# Power_And_Voltage_Shifters.net
KiCad netlist of a schematic drawn in Altium Designer
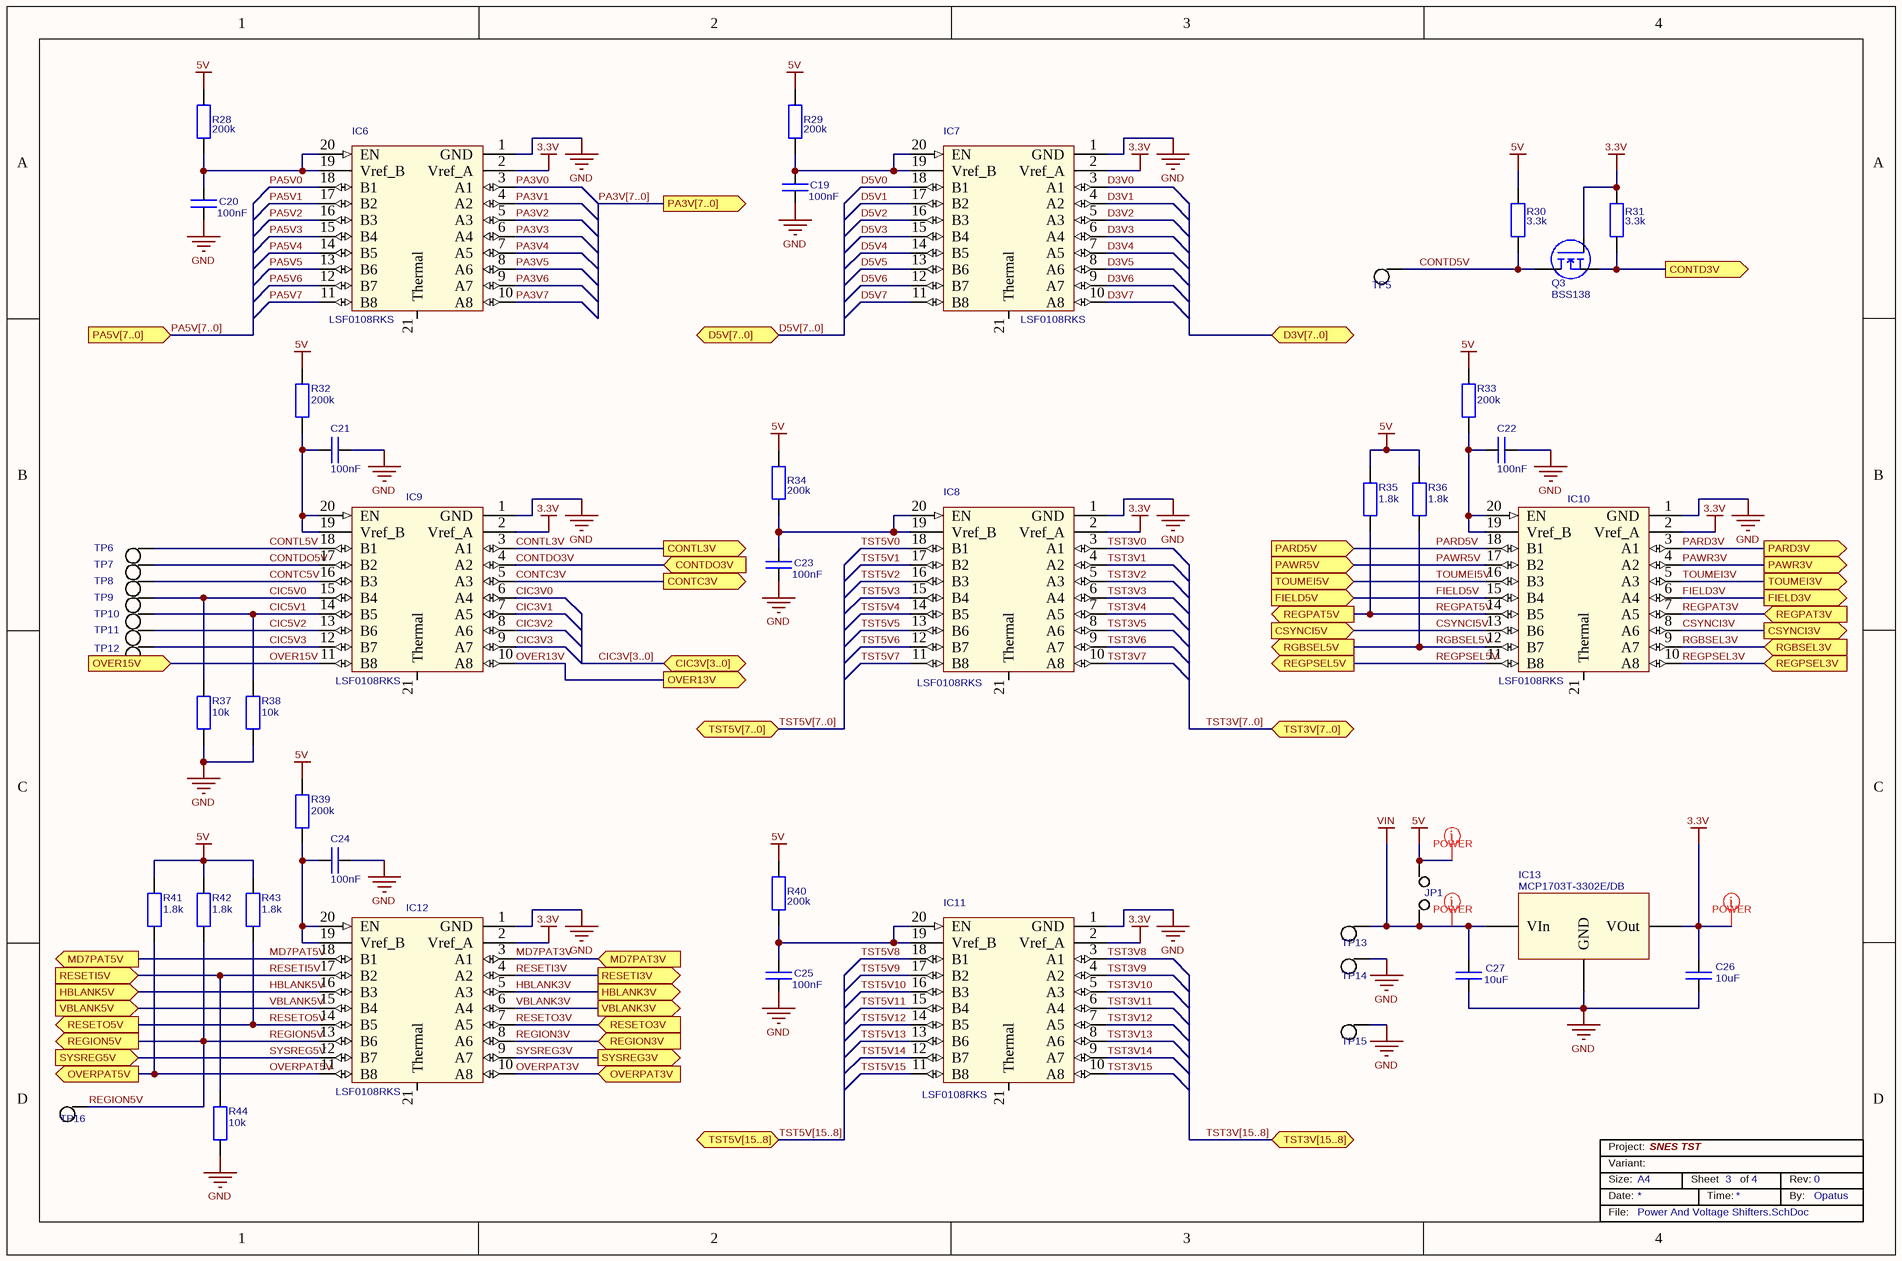
[diagram p0: Power And Voltage Shifters.SchDoc]

(export (version "E")
  (design (tool "Eeschema 10.0.6"))
  (components
    (comp (ref "C19")
      (value "100nF")
      (footprint "Cap_0402_Chip")
      (fields
        (field (name "TOLERANCE") "±20%")
        (field (name "Comment") "Ceramic Capacitor 100nF 10V ±20% X7R 0402")
      )
      (libsource (lib "PCB") (part "Capacitor"))
    )
    (comp (ref "C20")
      (value "100nF")
      (footprint "Cap_0402_Chip")
      (fields
        (field (name "TOLERANCE") "±20%")
        (field (name "Comment") "Ceramic Capacitor 100nF 10V ±20% X7R 0402")
      )
      (libsource (lib "PCB") (part "Capacitor"))
    )
    (comp (ref "C21")
      (value "100nF")
      (footprint "Cap_0402_Chip")
      (fields
        (field (name "TOLERANCE") "±20%")
        (field (name "Comment") "Ceramic Capacitor 100nF 10V ±20% X7R 0402")
      )
      (libsource (lib "PCB") (part "Capacitor"))
    )
    (comp (ref "C22")
      (value "100nF")
      (footprint "Cap_0402_Chip")
      (fields
        (field (name "TOLERANCE") "±20%")
        (field (name "Comment") "Ceramic Capacitor 100nF 10V ±20% X7R 0402")
      )
      (libsource (lib "PCB") (part "Capacitor"))
    )
    (comp (ref "C23")
      (value "100nF")
      (footprint "Cap_0402_Chip")
      (fields
        (field (name "TOLERANCE") "±20%")
        (field (name "Comment") "Ceramic Capacitor 100nF 10V ±20% X7R 0402")
      )
      (libsource (lib "PCB") (part "Capacitor"))
    )
    (comp (ref "C24")
      (value "100nF")
      (footprint "Cap_0402_Chip")
      (fields
        (field (name "TOLERANCE") "±20%")
        (field (name "Comment") "Ceramic Capacitor 100nF 10V ±20% X7R 0402")
      )
      (libsource (lib "PCB") (part "Capacitor"))
    )
    (comp (ref "C25")
      (value "100nF")
      (footprint "Cap_0402_Chip")
      (fields
        (field (name "TOLERANCE") "±20%")
        (field (name "Comment") "Ceramic Capacitor 100nF 10V ±20% X7R 0402")
      )
      (libsource (lib "PCB") (part "Capacitor"))
    )
    (comp (ref "C26")
      (value "10uF")
      (footprint "Cap_0805_Chip")
      (fields
        (field (name "TOLERANCE") "±20%")
        (field (name "Comment") "Ceramic Capacitor 10uF 10V ±20% X7R 0805")
      )
      (libsource (lib "PCB") (part "Capacitor"))
    )
    (comp (ref "C27")
      (value "10uF")
      (footprint "Cap_1206_Chip")
      (fields
        (field (name "TOLERANCE") "±20%")
        (field (name "Comment") "Ceramic Capacitor 10uF 25V ±20% X7R 1206")
      )
      (libsource (lib "PCB") (part "Capacitor"))
    )
    (comp (ref "IC6")
      (value "LSF0108")
      (footprint "VQFN20")
      (description "8-bit level shifter")
      (fields (field (name "MANUFACTURER_PART_NUMBER") "LSF0108RKS"))
      (libsource (lib "PCB") (part "LSF0108DCUR"))
    )
    (comp (ref "IC7")
      (value "LSF0108")
      (footprint "VQFN20")
      (description "8-bit level shifter")
      (fields (field (name "MANUFACTURER_PART_NUMBER") "LSF0108RKS"))
      (libsource (lib "PCB") (part "LSF0108DCUR"))
    )
    (comp (ref "IC8")
      (value "LSF0108")
      (footprint "VQFN20")
      (description "8-bit level shifter")
      (fields (field (name "MANUFACTURER_PART_NUMBER") "LSF0108RKS"))
      (libsource (lib "PCB") (part "LSF0108DCUR"))
    )
    (comp (ref "IC9")
      (value "LSF0108")
      (footprint "VQFN20")
      (description "8-bit level shifter")
      (fields (field (name "MANUFACTURER_PART_NUMBER") "LSF0108RKS"))
      (libsource (lib "PCB") (part "LSF0108DCUR"))
    )
    (comp (ref "IC10")
      (value "LSF0108")
      (footprint "VQFN20")
      (description "8-bit level shifter")
      (fields (field (name "MANUFACTURER_PART_NUMBER") "LSF0108RKS"))
      (libsource (lib "PCB") (part "LSF0108DCUR"))
    )
    (comp (ref "IC11")
      (value "LSF0108")
      (footprint "VQFN20")
      (description "8-bit level shifter")
      (fields (field (name "MANUFACTURER_PART_NUMBER") "LSF0108RKS"))
      (libsource (lib "PCB") (part "LSF0108DCUR"))
    )
    (comp (ref "IC12")
      (value "LSF0108")
      (footprint "VQFN20")
      (description "8-bit level shifter")
      (fields (field (name "MANUFACTURER_PART_NUMBER") "LSF0108RKS"))
      (libsource (lib "PCB") (part "LSF0108DCUR"))
    )
    (comp (ref "IC13")
      (value "MCP1703T")
      (footprint "SOT223-3")
      (description "3.3V Regulator")
      (fields (field (name "MANUFACTURER_PART_NUMBER") "MCP1703T-3302E/DB"))
      (libsource (lib "PCB") (part "MCP1703 SOT223"))
    )
    (comp (ref "JP1") (value "Jumper") (footprint "Jumper Big") (libsource (lib "PCB") (part "Jumper")))
    (comp (ref "Q3") (value "BSS138") (footprint "SOT23_FET") (libsource (lib "PCB") (part "Mosfet N")))
    (comp (ref "R28")
      (value "200k")
      (footprint "Res_0402_Chip")
      (fields (field (name "TOLERANCE") "±1%") (field (name "Comment") "Resistor 200k 0402 ±1%"))
      (libsource (lib "PCB") (part "R"))
    )
    (comp (ref "R29")
      (value "200k")
      (footprint "Res_0402_Chip")
      (fields (field (name "TOLERANCE") "±1%") (field (name "Comment") "Resistor 200k 0402 ±1%"))
      (libsource (lib "PCB") (part "R"))
    )
    (comp (ref "R30")
      (value "3.3k")
      (footprint "Res_0402_Chip")
      (fields (field (name "TOLERANCE") "±1%") (field (name "Comment") "Resistor 3.3k 0402 ±1%"))
      (libsource (lib "PCB") (part "R"))
    )
    (comp (ref "R31")
      (value "3.3k")
      (footprint "Res_0402_Chip")
      (fields (field (name "TOLERANCE") "±1%") (field (name "Comment") "Resistor 3.3k 0402 ±1%"))
      (libsource (lib "PCB") (part "R"))
    )
    (comp (ref "R32")
      (value "200k")
      (footprint "Res_0402_Chip")
      (fields (field (name "TOLERANCE") "±1%") (field (name "Comment") "Resistor 200k 0402 ±1%"))
      (libsource (lib "") (part "R_1"))
    )
    (comp (ref "R33")
      (value "200k")
      (footprint "Res_0402_Chip")
      (fields (field (name "TOLERANCE") "±1%") (field (name "Comment") "Resistor 200k 0402 ±1%"))
      (libsource (lib "") (part "R_1"))
    )
    (comp (ref "R34")
      (value "200k")
      (footprint "Res_0402_Chip")
      (fields (field (name "TOLERANCE") "±1%") (field (name "Comment") "Resistor 200k 0402 ±1%"))
      (libsource (lib "PCB") (part "R"))
    )
    (comp (ref "R35")
      (value "1.8k")
      (footprint "Res_0402_Chip")
      (fields (field (name "TOLERANCE") "±1%") (field (name "Comment") "Resistor 1.8k 0402 ±1%"))
      (libsource (lib "") (part "R_1"))
    )
    (comp (ref "R36")
      (value "1.8k")
      (footprint "Res_0402_Chip")
      (fields (field (name "TOLERANCE") "±1%") (field (name "Comment") "Resistor 1.8k 0402 ±1%"))
      (libsource (lib "") (part "R_1"))
    )
    (comp (ref "R37")
      (value "10k")
      (footprint "Res_0402_Chip")
      (fields (field (name "TOLERANCE") "±1%") (field (name "Comment") "Resistor 10k 0402 ±1%"))
      (libsource (lib "PCB") (part "R"))
    )
    (comp (ref "R38")
      (value "10k")
      (footprint "Res_0402_Chip")
      (fields (field (name "TOLERANCE") "±1%") (field (name "Comment") "Resistor 10k 0402 ±1%"))
      (libsource (lib "PCB") (part "R"))
    )
    (comp (ref "R39")
      (value "200k")
      (footprint "Res_0402_Chip")
      (fields (field (name "TOLERANCE") "±1%") (field (name "Comment") "Resistor 200k 0402 ±1%"))
      (libsource (lib "PCB") (part "R"))
    )
    (comp (ref "R40")
      (value "200k")
      (footprint "Res_0402_Chip")
      (fields (field (name "TOLERANCE") "±1%") (field (name "Comment") "Resistor 200k 0402 ±1%"))
      (libsource (lib "PCB") (part "R"))
    )
    (comp (ref "R41")
      (value "1.8k")
      (footprint "Res_0402_Chip")
      (fields (field (name "TOLERANCE") "±1%") (field (name "Comment") "Resistor 1.8k 0402 ±1%"))
      (libsource (lib "") (part "R_1"))
    )
    (comp (ref "R42")
      (value "1.8k")
      (footprint "Res_0402_Chip")
      (fields (field (name "TOLERANCE") "±1%") (field (name "Comment") "Resistor 1.8k 0402 ±1%"))
      (libsource (lib "") (part "R_1"))
    )
    (comp (ref "R43")
      (value "1.8k")
      (footprint "Res_0402_Chip")
      (fields (field (name "TOLERANCE") "±1%") (field (name "Comment") "Resistor 1.8k 0402 ±1%"))
      (libsource (lib "") (part "R_1"))
    )
    (comp (ref "R44")
      (value "10k")
      (footprint "Res_0402_Chip")
      (fields (field (name "TOLERANCE") "±1%") (field (name "Comment") "Resistor 10k 0402 ±1%"))
      (libsource (lib "") (part "R_1"))
    )
    (comp (ref "TP5")
      (value "Pin Connector")
      (footprint "Pin Connector Small")
      (libsource (lib "PCB") (part "Pin Connector"))
    )
    (comp (ref "TP6")
      (value "Pin Connector")
      (footprint "Pin Connector Small")
      (libsource (lib "PCB") (part "Pin Connector"))
    )
    (comp (ref "TP7")
      (value "Pin Connector")
      (footprint "Pin Connector Small")
      (libsource (lib "PCB") (part "Pin Connector"))
    )
    (comp (ref "TP8")
      (value "Pin Connector")
      (footprint "Pin Connector Small")
      (libsource (lib "PCB") (part "Pin Connector"))
    )
    (comp (ref "TP9")
      (value "Pin Connector")
      (footprint "Pin Connector Small")
      (libsource (lib "PCB") (part "Pin Connector"))
    )
    (comp (ref "TP10")
      (value "Pin Connector")
      (footprint "Pin Connector Small")
      (libsource (lib "PCB") (part "Pin Connector"))
    )
    (comp (ref "TP11")
      (value "Pin Connector")
      (footprint "Pin Connector Small")
      (libsource (lib "PCB") (part "Pin Connector"))
    )
    (comp (ref "TP12")
      (value "Pin Connector")
      (footprint "Pin Connector Small")
      (libsource (lib "PCB") (part "Pin Connector"))
    )
    (comp (ref "TP13")
      (value "Pin Connector")
      (footprint "Pin Connector Small")
      (libsource (lib "PCB") (part "Pin Connector"))
    )
    (comp (ref "TP14")
      (value "Pin Connector")
      (footprint "Pin Connector Small")
      (libsource (lib "PCB") (part "Pin Connector"))
    )
    (comp (ref "TP15")
      (value "Pin Connector")
      (footprint "Pin Connector Small")
      (libsource (lib "PCB") (part "Pin Connector"))
    )
    (comp (ref "TP16")
      (value "Pin Connector")
      (footprint "Pin Connector Small")
      (libsource (lib "PCB") (part "Pin Connector"))
    )
  )
  (nets
    (net (code "1") (name "/CIC3V0") (class "Default")
      (node (ref "IC9") (pin "6") (pinfunction "A4_6") (pintype "bidirectional"))
    )
    (net (code "2") (name "/CIC3V1") (class "Default")
      (node (ref "IC9") (pin "7") (pinfunction "A5_7") (pintype "bidirectional"))
    )
    (net (code "3") (name "/CIC3V2") (class "Default")
      (node (ref "IC9") (pin "8") (pinfunction "A6_8") (pintype "bidirectional"))
    )
    (net (code "4") (name "/CIC3V3") (class "Default")
      (node (ref "IC9") (pin "9") (pinfunction "A7_9") (pintype "bidirectional"))
    )
    (net (code "6") (name "/CIC5V0") (class "Default")
      (node (ref "IC9") (pin "15") (pinfunction "B4_15") (pintype "bidirectional"))
      (node (ref "R37") (pin "2") (pintype "passive"))
      (node (ref "TP9") (pin "1") (pinfunction "0_1") (pintype "passive"))
    )
    (net (code "7") (name "/CIC5V1") (class "Default")
      (node (ref "IC9") (pin "14") (pinfunction "B5_14") (pintype "bidirectional"))
      (node (ref "R38") (pin "2") (pintype "passive"))
      (node (ref "TP10") (pin "1") (pinfunction "0_1") (pintype "passive"))
    )
    (net (code "8") (name "/CIC5V2") (class "Default")
      (node (ref "IC9") (pin "13") (pinfunction "B6_13") (pintype "bidirectional"))
      (node (ref "TP11") (pin "1") (pinfunction "0_1") (pintype "passive"))
    )
    (net (code "9") (name "/CIC5V3") (class "Default")
      (node (ref "IC9") (pin "12") (pinfunction "B7_12") (pintype "bidirectional"))
      (node (ref "TP12") (pin "1") (pinfunction "0_1") (pintype "passive"))
    )
    (net (code "10") (name "/CONTC3V") (class "Default")
      (node (ref "IC9") (pin "5") (pinfunction "A3_5") (pintype "bidirectional"))
    )
    (net (code "11") (name "/CONTC5V") (class "Default")
      (node (ref "IC9") (pin "16") (pinfunction "B3_16") (pintype "bidirectional"))
      (node (ref "TP8") (pin "1") (pinfunction "0_1") (pintype "passive"))
    )
    (net (code "12") (name "/CONTD3V") (class "Default")
      (node (ref "Q3") (pin "S") (pinfunction "S_S") (pintype "passive"))
      (node (ref "R31") (pin "1") (pintype "passive"))
    )
    (net (code "13") (name "/CONTD5V") (class "Default")
      (node (ref "Q3") (pin "D") (pinfunction "D_D") (pintype "passive"))
      (node (ref "R30") (pin "1") (pintype "passive"))
      (node (ref "TP5") (pin "1") (pinfunction "0_1") (pintype "passive"))
    )
    (net (code "14") (name "/CONTDO3V") (class "Default")
      (node (ref "IC9") (pin "4") (pinfunction "A2_4") (pintype "bidirectional"))
    )
    (net (code "15") (name "/CONTDO5V") (class "Default")
      (node (ref "IC9") (pin "17") (pinfunction "B2_17") (pintype "bidirectional"))
      (node (ref "TP7") (pin "1") (pinfunction "0_1") (pintype "passive"))
    )
    (net (code "16") (name "/CONTL3V") (class "Default")
      (node (ref "IC9") (pin "3") (pinfunction "A1_3") (pintype "bidirectional"))
    )
    (net (code "17") (name "/CONTL5V") (class "Default")
      (node (ref "IC9") (pin "18") (pinfunction "B1_18") (pintype "bidirectional"))
      (node (ref "TP6") (pin "1") (pinfunction "0_1") (pintype "passive"))
    )
    (net (code "18") (name "/CSYNCI3V") (class "Default")
      (node (ref "IC10") (pin "8") (pinfunction "A6_8") (pintype "bidirectional"))
    )
    (net (code "19") (name "/CSYNCI5V") (class "Default")
      (node (ref "IC10") (pin "13") (pinfunction "B6_13") (pintype "bidirectional"))
    )
    (net (code "20") (name "/D3V0") (class "Default")
      (node (ref "IC7") (pin "3") (pinfunction "A1_3") (pintype "bidirectional"))
    )
    (net (code "21") (name "/D3V1") (class "Default")
      (node (ref "IC7") (pin "4") (pinfunction "A2_4") (pintype "bidirectional"))
    )
    (net (code "22") (name "/D3V2") (class "Default")
      (node (ref "IC7") (pin "5") (pinfunction "A3_5") (pintype "bidirectional"))
    )
    (net (code "23") (name "/D3V3") (class "Default")
      (node (ref "IC7") (pin "6") (pinfunction "A4_6") (pintype "bidirectional"))
    )
    (net (code "24") (name "/D3V4") (class "Default")
      (node (ref "IC7") (pin "7") (pinfunction "A5_7") (pintype "bidirectional"))
    )
    (net (code "25") (name "/D3V5") (class "Default")
      (node (ref "IC7") (pin "8") (pinfunction "A6_8") (pintype "bidirectional"))
    )
    (net (code "26") (name "/D3V6") (class "Default")
      (node (ref "IC7") (pin "9") (pinfunction "A7_9") (pintype "bidirectional"))
    )
    (net (code "27") (name "/D3V7") (class "Default")
      (node (ref "IC7") (pin "10") (pinfunction "A8_10") (pintype "bidirectional"))
    )
    (net (code "29") (name "/D5V0") (class "Default")
      (node (ref "IC7") (pin "18") (pinfunction "B1_18") (pintype "bidirectional"))
    )
    (net (code "30") (name "/D5V1") (class "Default")
      (node (ref "IC7") (pin "17") (pinfunction "B2_17") (pintype "bidirectional"))
    )
    (net (code "31") (name "/D5V2") (class "Default")
      (node (ref "IC7") (pin "16") (pinfunction "B3_16") (pintype "bidirectional"))
    )
    (net (code "32") (name "/D5V3") (class "Default")
      (node (ref "IC7") (pin "15") (pinfunction "B4_15") (pintype "bidirectional"))
    )
    (net (code "33") (name "/D5V4") (class "Default")
      (node (ref "IC7") (pin "14") (pinfunction "B5_14") (pintype "bidirectional"))
    )
    (net (code "34") (name "/D5V5") (class "Default")
      (node (ref "IC7") (pin "13") (pinfunction "B6_13") (pintype "bidirectional"))
    )
    (net (code "35") (name "/D5V6") (class "Default")
      (node (ref "IC7") (pin "12") (pinfunction "B7_12") (pintype "bidirectional"))
    )
    (net (code "36") (name "/D5V7") (class "Default")
      (node (ref "IC7") (pin "11") (pinfunction "B8_11") (pintype "bidirectional"))
    )
    (net (code "38") (name "/FIELD3V") (class "Default")
      (node (ref "IC10") (pin "6") (pinfunction "A4_6") (pintype "bidirectional"))
    )
    (net (code "39") (name "/FIELD5V") (class "Default")
      (node (ref "IC10") (pin "15") (pinfunction "B4_15") (pintype "bidirectional"))
    )
    (net (code "40") (name "/HBLANK3V") (class "Default")
      (node (ref "IC12") (pin "5") (pinfunction "A3_5") (pintype "bidirectional"))
    )
    (net (code "41") (name "/HBLANK5V") (class "Default")
      (node (ref "IC12") (pin "16") (pinfunction "B3_16") (pintype "bidirectional"))
    )
    (net (code "42") (name "/MD7PAT3V") (class "Default")
      (node (ref "IC12") (pin "3") (pinfunction "A1_3") (pintype "bidirectional"))
    )
    (net (code "43") (name "/MD7PAT5V") (class "Default")
      (node (ref "IC12") (pin "18") (pinfunction "B1_18") (pintype "bidirectional"))
    )
    (net (code "44") (name "/OVER13V") (class "Default")
      (node (ref "IC9") (pin "10") (pinfunction "A8_10") (pintype "bidirectional"))
    )
    (net (code "45") (name "/OVER15V") (class "Default")
      (node (ref "IC9") (pin "11") (pinfunction "B8_11") (pintype "bidirectional"))
    )
    (net (code "46") (name "/OVERPAT3V") (class "Default")
      (node (ref "IC12") (pin "10") (pinfunction "A8_10") (pintype "bidirectional"))
    )
    (net (code "47") (name "/OVERPAT5V") (class "Default")
      (node (ref "IC12") (pin "11") (pinfunction "B8_11") (pintype "bidirectional"))
      (node (ref "R41") (pin "2") (pintype "passive"))
    )
    (net (code "48") (name "/PA3V0") (class "Default")
      (node (ref "IC6") (pin "3") (pinfunction "A1_3") (pintype "bidirectional"))
    )
    (net (code "49") (name "/PA3V1") (class "Default")
      (node (ref "IC6") (pin "4") (pinfunction "A2_4") (pintype "bidirectional"))
    )
    (net (code "50") (name "/PA3V2") (class "Default")
      (node (ref "IC6") (pin "5") (pinfunction "A3_5") (pintype "bidirectional"))
    )
    (net (code "51") (name "/PA3V3") (class "Default")
      (node (ref "IC6") (pin "6") (pinfunction "A4_6") (pintype "bidirectional"))
    )
    (net (code "52") (name "/PA3V4") (class "Default")
      (node (ref "IC6") (pin "7") (pinfunction "A5_7") (pintype "bidirectional"))
    )
    (net (code "53") (name "/PA3V5") (class "Default")
      (node (ref "IC6") (pin "8") (pinfunction "A6_8") (pintype "bidirectional"))
    )
    (net (code "54") (name "/PA3V6") (class "Default")
      (node (ref "IC6") (pin "9") (pinfunction "A7_9") (pintype "bidirectional"))
    )
    (net (code "55") (name "/PA3V7") (class "Default")
      (node (ref "IC6") (pin "10") (pinfunction "A8_10") (pintype "bidirectional"))
    )
    (net (code "57") (name "/PA5V0") (class "Default")
      (node (ref "IC6") (pin "18") (pinfunction "B1_18") (pintype "bidirectional"))
    )
    (net (code "58") (name "/PA5V1") (class "Default")
      (node (ref "IC6") (pin "17") (pinfunction "B2_17") (pintype "bidirectional"))
    )
    (net (code "59") (name "/PA5V2") (class "Default")
      (node (ref "IC6") (pin "16") (pinfunction "B3_16") (pintype "bidirectional"))
    )
    (net (code "60") (name "/PA5V3") (class "Default")
      (node (ref "IC6") (pin "15") (pinfunction "B4_15") (pintype "bidirectional"))
    )
    (net (code "61") (name "/PA5V4") (class "Default")
      (node (ref "IC6") (pin "14") (pinfunction "B5_14") (pintype "bidirectional"))
    )
    (net (code "62") (name "/PA5V5") (class "Default")
      (node (ref "IC6") (pin "13") (pinfunction "B6_13") (pintype "bidirectional"))
    )
    (net (code "63") (name "/PA5V6") (class "Default")
      (node (ref "IC6") (pin "12") (pinfunction "B7_12") (pintype "bidirectional"))
    )
    (net (code "64") (name "/PA5V7") (class "Default")
      (node (ref "IC6") (pin "11") (pinfunction "B8_11") (pintype "bidirectional"))
    )
    (net (code "66") (name "/PARD3V") (class "Default")
      (node (ref "IC10") (pin "3") (pinfunction "A1_3") (pintype "bidirectional"))
    )
    (net (code "67") (name "/PARD5V") (class "Default")
      (node (ref "IC10") (pin "18") (pinfunction "B1_18") (pintype "bidirectional"))
    )
    (net (code "68") (name "/PAWR3V") (class "Default")
      (node (ref "IC10") (pin "4") (pinfunction "A2_4") (pintype "bidirectional"))
    )
    (net (code "69") (name "/PAWR5V") (class "Default")
      (node (ref "IC10") (pin "17") (pinfunction "B2_17") (pintype "bidirectional"))
    )
    (net (code "70") (name "/REGION3V") (class "Default")
      (node (ref "IC12") (pin "8") (pinfunction "A6_8") (pintype "bidirectional"))
    )
    (net (code "71") (name "/REGION5V") (class "Default")
      (node (ref "IC12") (pin "13") (pinfunction "B6_13") (pintype "bidirectional"))
      (node (ref "R42") (pin "2") (pintype "passive"))
      (node (ref "TP16") (pin "1") (pinfunction "0_1") (pintype "passive"))
    )
    (net (code "72") (name "/REGPAT3V") (class "Default")
      (node (ref "IC10") (pin "7") (pinfunction "A5_7") (pintype "bidirectional"))
    )
    (net (code "73") (name "/REGPAT5V") (class "Default")
      (node (ref "IC10") (pin "14") (pinfunction "B5_14") (pintype "bidirectional"))
      (node (ref "R35") (pin "2") (pintype "passive"))
    )
    (net (code "74") (name "/REGPSEL3V") (class "Default")
      (node (ref "IC10") (pin "10") (pinfunction "A8_10") (pintype "bidirectional"))
    )
    (net (code "75") (name "/REGPSEL5V") (class "Default")
      (node (ref "IC10") (pin "11") (pinfunction "B8_11") (pintype "bidirectional"))
    )
    (net (code "76") (name "/RESETI3V") (class "Default")
      (node (ref "IC12") (pin "4") (pinfunction "A2_4") (pintype "bidirectional"))
    )
    (net (code "77") (name "/RESETI5V") (class "Default")
      (node (ref "IC12") (pin "17") (pinfunction "B2_17") (pintype "bidirectional"))
      (node (ref "R44") (pin "1") (pintype "passive"))
    )
    (net (code "78") (name "/RESETO3V") (class "Default")
      (node (ref "IC12") (pin "7") (pinfunction "A5_7") (pintype "bidirectional"))
    )
    (net (code "79") (name "/RESETO5V") (class "Default")
      (node (ref "IC12") (pin "14") (pinfunction "B5_14") (pintype "bidirectional"))
      (node (ref "R43") (pin "2") (pintype "passive"))
    )
    (net (code "80") (name "/RGBSEL3V") (class "Default")
      (node (ref "IC10") (pin "9") (pinfunction "A7_9") (pintype "bidirectional"))
    )
    (net (code "81") (name "/RGBSEL5V") (class "Default")
      (node (ref "IC10") (pin "12") (pinfunction "B7_12") (pintype "bidirectional"))
      (node (ref "R36") (pin "2") (pintype "passive"))
    )
    (net (code "82") (name "/SYSREG3V") (class "Default")
      (node (ref "IC12") (pin "9") (pinfunction "A7_9") (pintype "bidirectional"))
    )
    (net (code "83") (name "/SYSREG5V") (class "Default")
      (node (ref "IC12") (pin "12") (pinfunction "B7_12") (pintype "bidirectional"))
    )
    (net (code "84") (name "/TOUMEI3V") (class "Default")
      (node (ref "IC10") (pin "5") (pinfunction "A3_5") (pintype "bidirectional"))
    )
    (net (code "85") (name "/TOUMEI5V") (class "Default")
      (node (ref "IC10") (pin "16") (pinfunction "B3_16") (pintype "bidirectional"))
    )
    (net (code "86") (name "/TST3V0") (class "Default")
      (node (ref "IC8") (pin "3") (pinfunction "A1_3") (pintype "bidirectional"))
    )
    (net (code "87") (name "/TST3V1") (class "Default")
      (node (ref "IC8") (pin "4") (pinfunction "A2_4") (pintype "bidirectional"))
    )
    (net (code "88") (name "/TST3V2") (class "Default")
      (node (ref "IC8") (pin "5") (pinfunction "A3_5") (pintype "bidirectional"))
    )
    (net (code "89") (name "/TST3V3") (class "Default")
      (node (ref "IC8") (pin "6") (pinfunction "A4_6") (pintype "bidirectional"))
    )
    (net (code "90") (name "/TST3V4") (class "Default")
      (node (ref "IC8") (pin "7") (pinfunction "A5_7") (pintype "bidirectional"))
    )
    (net (code "91") (name "/TST3V5") (class "Default")
      (node (ref "IC8") (pin "8") (pinfunction "A6_8") (pintype "bidirectional"))
    )
    (net (code "92") (name "/TST3V6") (class "Default")
      (node (ref "IC8") (pin "9") (pinfunction "A7_9") (pintype "bidirectional"))
    )
    (net (code "93") (name "/TST3V7") (class "Default")
      (node (ref "IC8") (pin "10") (pinfunction "A8_10") (pintype "bidirectional"))
    )
    (net (code "94") (name "/TST3V8") (class "Default")
      (node (ref "IC11") (pin "3") (pinfunction "A1_3") (pintype "bidirectional"))
    )
    (net (code "95") (name "/TST3V9") (class "Default")
      (node (ref "IC11") (pin "4") (pinfunction "A2_4") (pintype "bidirectional"))
    )
    (net (code "96") (name "/TST3V10") (class "Default")
      (node (ref "IC11") (pin "5") (pinfunction "A3_5") (pintype "bidirectional"))
    )
    (net (code "97") (name "/TST3V11") (class "Default")
      (node (ref "IC11") (pin "6") (pinfunction "A4_6") (pintype "bidirectional"))
    )
    (net (code "98") (name "/TST3V12") (class "Default")
      (node (ref "IC11") (pin "7") (pinfunction "A5_7") (pintype "bidirectional"))
    )
    (net (code "99") (name "/TST3V13") (class "Default")
      (node (ref "IC11") (pin "8") (pinfunction "A6_8") (pintype "bidirectional"))
    )
    (net (code "100") (name "/TST3V14") (class "Default")
      (node (ref "IC11") (pin "9") (pinfunction "A7_9") (pintype "bidirectional"))
    )
    (net (code "101") (name "/TST3V15") (class "Default")
      (node (ref "IC11") (pin "10") (pinfunction "A8_10") (pintype "bidirectional"))
    )
    (net (code "104") (name "/TST5V0") (class "Default")
      (node (ref "IC8") (pin "18") (pinfunction "B1_18") (pintype "bidirectional"))
    )
    (net (code "105") (name "/TST5V1") (class "Default")
      (node (ref "IC8") (pin "17") (pinfunction "B2_17") (pintype "bidirectional"))
    )
    (net (code "106") (name "/TST5V2") (class "Default")
      (node (ref "IC8") (pin "16") (pinfunction "B3_16") (pintype "bidirectional"))
    )
    (net (code "107") (name "/TST5V3") (class "Default")
      (node (ref "IC8") (pin "15") (pinfunction "B4_15") (pintype "bidirectional"))
    )
    (net (code "108") (name "/TST5V4") (class "Default")
      (node (ref "IC8") (pin "14") (pinfunction "B5_14") (pintype "bidirectional"))
    )
    (net (code "109") (name "/TST5V5") (class "Default")
      (node (ref "IC8") (pin "13") (pinfunction "B6_13") (pintype "bidirectional"))
    )
    (net (code "110") (name "/TST5V6") (class "Default")
      (node (ref "IC8") (pin "12") (pinfunction "B7_12") (pintype "bidirectional"))
    )
    (net (code "111") (name "/TST5V7") (class "Default")
      (node (ref "IC8") (pin "11") (pinfunction "B8_11") (pintype "bidirectional"))
    )
    (net (code "112") (name "/TST5V8") (class "Default")
      (node (ref "IC11") (pin "18") (pinfunction "B1_18") (pintype "bidirectional"))
    )
    (net (code "113") (name "/TST5V9") (class "Default")
      (node (ref "IC11") (pin "17") (pinfunction "B2_17") (pintype "bidirectional"))
    )
    (net (code "114") (name "/TST5V10") (class "Default")
      (node (ref "IC11") (pin "16") (pinfunction "B3_16") (pintype "bidirectional"))
    )
    (net (code "115") (name "/TST5V11") (class "Default")
      (node (ref "IC11") (pin "15") (pinfunction "B4_15") (pintype "bidirectional"))
    )
    (net (code "116") (name "/TST5V12") (class "Default")
      (node (ref "IC11") (pin "14") (pinfunction "B5_14") (pintype "bidirectional"))
    )
    (net (code "117") (name "/TST5V13") (class "Default")
      (node (ref "IC11") (pin "13") (pinfunction "B6_13") (pintype "bidirectional"))
    )
    (net (code "118") (name "/TST5V14") (class "Default")
      (node (ref "IC11") (pin "12") (pinfunction "B7_12") (pintype "bidirectional"))
    )
    (net (code "119") (name "/TST5V15") (class "Default")
      (node (ref "IC11") (pin "11") (pinfunction "B8_11") (pintype "bidirectional"))
    )
    (net (code "122") (name "/VBLANK3V") (class "Default")
      (node (ref "IC12") (pin "6") (pinfunction "A4_6") (pintype "bidirectional"))
    )
    (net (code "123") (name "/VBLANK5V") (class "Default")
      (node (ref "IC12") (pin "15") (pinfunction "B4_15") (pintype "bidirectional"))
    )
    (net (code "124") (name "3.3V") (class "Default")
      (node (ref "C26") (pin "2") (pintype "passive"))
      (node (ref "IC10") (pin "2") (pinfunction "Vref_A_2") (pintype "power_in"))
      (node (ref "IC11") (pin "2") (pinfunction "Vref_A_2") (pintype "power_in"))
      (node (ref "IC12") (pin "2") (pinfunction "Vref_A_2") (pintype "power_in"))
      (node (ref "IC13") (pin "3") (pinfunction "VOut_3") (pintype "passive"))
      (node (ref "IC6") (pin "2") (pinfunction "Vref_A_2") (pintype "power_in"))
      (node (ref "IC7") (pin "2") (pinfunction "Vref_A_2") (pintype "power_in"))
      (node (ref "IC8") (pin "2") (pinfunction "Vref_A_2") (pintype "power_in"))
      (node (ref "IC9") (pin "2") (pinfunction "Vref_A_2") (pintype "power_in"))
      (node (ref "Q3") (pin "G") (pinfunction "G_G") (pintype "passive"))
      (node (ref "R31") (pin "2") (pintype "passive"))
    )
    (net (code "125") (name "5V") (class "Default")
      (node (ref "JP1") (pin "1") (pinfunction "0_1") (pintype "passive"))
      (node (ref "R28") (pin "2") (pintype "passive"))
      (node (ref "R29") (pin "2") (pintype "passive"))
      (node (ref "R30") (pin "2") (pintype "passive"))
      (node (ref "R32") (pin "1") (pintype "passive"))
      (node (ref "R33") (pin "1") (pintype "passive"))
      (node (ref "R34") (pin "2") (pintype "passive"))
      (node (ref "R35") (pin "1") (pintype "passive"))
      (node (ref "R36") (pin "1") (pintype "passive"))
      (node (ref "R39") (pin "2") (pintype "passive"))
      (node (ref "R40") (pin "2") (pintype "passive"))
      (node (ref "R41") (pin "1") (pintype "passive"))
      (node (ref "R42") (pin "1") (pintype "passive"))
      (node (ref "R43") (pin "1") (pintype "passive"))
    )
    (net (code "126") (name "GND") (class "Default")
      (node (ref "C19") (pin "2") (pintype "passive"))
      (node (ref "C20") (pin "2") (pintype "passive"))
      (node (ref "C21") (pin "1") (pintype "passive"))
      (node (ref "C22") (pin "1") (pintype "passive"))
      (node (ref "C23") (pin "2") (pintype "passive"))
      (node (ref "C24") (pin "2") (pintype "passive"))
      (node (ref "C25") (pin "2") (pintype "passive"))
      (node (ref "C26") (pin "1") (pintype "passive"))
      (node (ref "C27") (pin "1") (pintype "passive"))
      (node (ref "IC10") (pin "1") (pinfunction "GND_1") (pintype "power_in"))
      (node (ref "IC11") (pin "1") (pinfunction "GND_1") (pintype "power_in"))
      (node (ref "IC12") (pin "1") (pinfunction "GND_1") (pintype "power_in"))
      (node (ref "IC13") (pin "2") (pinfunction "GND_2") (pintype "passive"))
      (node (ref "IC6") (pin "1") (pinfunction "GND_1") (pintype "power_in"))
      (node (ref "IC7") (pin "1") (pinfunction "GND_1") (pintype "power_in"))
      (node (ref "IC8") (pin "1") (pinfunction "GND_1") (pintype "power_in"))
      (node (ref "IC9") (pin "1") (pinfunction "GND_1") (pintype "power_in"))
      (node (ref "R37") (pin "1") (pintype "passive"))
      (node (ref "R38") (pin "1") (pintype "passive"))
      (node (ref "R44") (pin "2") (pintype "passive"))
      (node (ref "TP14") (pin "1") (pinfunction "0_1") (pintype "passive"))
      (node (ref "TP15") (pin "1") (pinfunction "0_1") (pintype "passive"))
    )
    (net (code "127") (name "Net-(IC6-EN)") (class "Default")
      (node (ref "C20") (pin "1") (pintype "passive"))
      (node (ref "IC6") (pin "19") (pinfunction "Vref_B_19") (pintype "power_in"))
      (node (ref "IC6") (pin "20") (pinfunction "EN_20") (pintype "input"))
      (node (ref "R28") (pin "1") (pintype "passive"))
    )
    (net (code "128") (name "Net-(IC7-EN)") (class "Default")
      (node (ref "C19") (pin "1") (pintype "passive"))
      (node (ref "IC7") (pin "19") (pinfunction "Vref_B_19") (pintype "power_in"))
      (node (ref "IC7") (pin "20") (pinfunction "EN_20") (pintype "input"))
      (node (ref "R29") (pin "1") (pintype "passive"))
    )
    (net (code "129") (name "Net-(IC8-EN)") (class "Default")
      (node (ref "C23") (pin "1") (pintype "passive"))
      (node (ref "IC8") (pin "19") (pinfunction "Vref_B_19") (pintype "power_in"))
      (node (ref "IC8") (pin "20") (pinfunction "EN_20") (pintype "input"))
      (node (ref "R34") (pin "1") (pintype "passive"))
    )
    (net (code "130") (name "Net-(IC9-EN)") (class "Default")
      (node (ref "C21") (pin "2") (pintype "passive"))
      (node (ref "IC9") (pin "19") (pinfunction "Vref_B_19") (pintype "power_in"))
      (node (ref "IC9") (pin "20") (pinfunction "EN_20") (pintype "input"))
      (node (ref "R32") (pin "2") (pintype "passive"))
    )
    (net (code "131") (name "Net-(IC10-EN)") (class "Default")
      (node (ref "C22") (pin "2") (pintype "passive"))
      (node (ref "IC10") (pin "19") (pinfunction "Vref_B_19") (pintype "power_in"))
      (node (ref "IC10") (pin "20") (pinfunction "EN_20") (pintype "input"))
      (node (ref "R33") (pin "2") (pintype "passive"))
    )
    (net (code "132") (name "Net-(IC11-EN)") (class "Default")
      (node (ref "C25") (pin "1") (pintype "passive"))
      (node (ref "IC11") (pin "19") (pinfunction "Vref_B_19") (pintype "power_in"))
      (node (ref "IC11") (pin "20") (pinfunction "EN_20") (pintype "input"))
      (node (ref "R40") (pin "1") (pintype "passive"))
    )
    (net (code "133") (name "Net-(IC12-EN)") (class "Default")
      (node (ref "C24") (pin "1") (pintype "passive"))
      (node (ref "IC12") (pin "19") (pinfunction "Vref_B_19") (pintype "power_in"))
      (node (ref "IC12") (pin "20") (pinfunction "EN_20") (pintype "input"))
      (node (ref "R39") (pin "1") (pintype "passive"))
    )
    (net (code "134") (name "VIN") (class "Default")
      (node (ref "C27") (pin "2") (pintype "passive"))
      (node (ref "IC13") (pin "1") (pinfunction "VIn_1") (pintype "passive"))
      (node (ref "JP1") (pin "2") (pinfunction "0_2") (pintype "passive"))
      (node (ref "TP13") (pin "1") (pinfunction "0_1") (pintype "passive"))
    )
    (net (code "135") (name "unconnected-(IC6-Thermal-Pad21)") (class "Default")
      (node (ref "IC6") (pin "21") (pinfunction "Thermal_21") (pintype "passive"))
    )
    (net (code "136") (name "unconnected-(IC7-Thermal-Pad21)") (class "Default")
      (node (ref "IC7") (pin "21") (pinfunction "Thermal_21") (pintype "passive"))
    )
    (net (code "137") (name "unconnected-(IC8-Thermal-Pad21)") (class "Default")
      (node (ref "IC8") (pin "21") (pinfunction "Thermal_21") (pintype "passive"))
    )
    (net (code "138") (name "unconnected-(IC9-Thermal-Pad21)") (class "Default")
      (node (ref "IC9") (pin "21") (pinfunction "Thermal_21") (pintype "passive"))
    )
    (net (code "139") (name "unconnected-(IC10-Thermal-Pad21)") (class "Default")
      (node (ref "IC10") (pin "21") (pinfunction "Thermal_21") (pintype "passive"))
    )
    (net (code "140") (name "unconnected-(IC11-Thermal-Pad21)") (class "Default")
      (node (ref "IC11") (pin "21") (pinfunction "Thermal_21") (pintype "passive"))
    )
    (net (code "141") (name "unconnected-(IC12-Thermal-Pad21)") (class "Default")
      (node (ref "IC12") (pin "21") (pinfunction "Thermal_21") (pintype "passive"))
    )
  )
)
